# 555_A-stable.net
KiCad netlist of a schematic drawn in Altium Designer
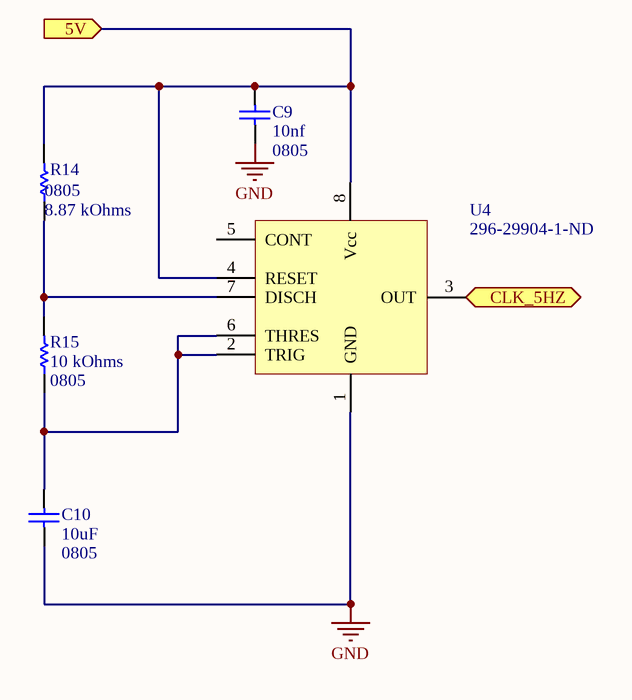
[diagram p0: 555_A-stable.SchDoc]

(export (version "E")
  (design (tool "Eeschema 10.0.6"))
  (components
    (comp (ref "C9")
      (value "CGA4C2C0G1H103J060AA")
      (footprint "CAP0805")
      (description "CAP CER 10000PF 50V C0G 0805")
      (fields
        (field (name "TOLERANCE") "±5%")
        (field (name "CAPACITANCE") "10nf")
        (field (name "PACKAGE / CASE") "0805")
      )
      (libsource (lib "Capacitors") (part "CGA4C2C0G1H103J060AA"))
    )
    (comp (ref "C10")
      (value "C2012JB1V106K125AC")
      (footprint "CAP0805")
      (description "CAP CER 10UF 35V JB 0805")
      (fields
        (field (name "TOLERANCE") "±20%")
        (field (name "CAPACITANCE") "10uF")
        (field (name "PACKAGE / CASE") "0805")
      )
      (libsource (lib "Capacitors") (part "C2012JB1V106K125AC"))
    )
    (comp (ref "R14")
      (value "ERJ-6ENF8871V")
      (footprint "RES0805")
      (description "RES SMD 8.87K OHM 1% 1/8W 0805")
      (fields
        (field (name "TOLERANCE") "±1%")
        (field (name "PACKAGE / CASE") "0805")
        (field (name "RESISTANCE") "8.87 kOhms")
      )
      (libsource (lib "Resistors") (part "ERJ-6ENF8871V"))
    )
    (comp (ref "R15")
      (value "RC0805FR-0710KL")
      (footprint "RES0805")
      (description "RES SMD 10K OHM 1% 1/8W 0805")
      (fields
        (field (name "MANUFACTURER") "Yageo")
        (field (name "TOLERANCE") "±1%")
        (field (name "RESISTANCE") "10 kOhms")
        (field (name "PACKAGE / CASE") "0805")
      )
      (libsource (lib "Resistors") (part "RC0805FR-0710KL"))
    )
    (comp (ref "U4")
      (value "NE555PWR")
      (footprint "TSOP65P650X120-8N")
      (description "IC OSC SGL TIMER 100KHZ 8TSSOP")
      (fields (field (name "SUPPLIER PART NUMBER 1") "296-29904-1-ND"))
      (libsource (lib "ICs") (part "NE555PWR"))
    )
  )
  (nets
    (net (code "1") (name "/5V") (class "Default")
      (node (ref "C9") (pin "2") (pinfunction "2_2") (pintype "passive"))
      (node (ref "R14") (pin "2") (pinfunction "2_2") (pintype "passive"))
      (node (ref "U4") (pin "4") (pinfunction "RESET_4") (pintype "passive"))
      (node (ref "U4") (pin "8") (pinfunction "Vcc_8") (pintype "passive"))
    )
    (net (code "2") (name "/CLK_5HZ") (class "Default")
      (node (ref "U4") (pin "3") (pinfunction "OUT_3") (pintype "passive"))
    )
    (net (code "3") (name "GND") (class "Default")
      (node (ref "C10") (pin "1") (pinfunction "1_1") (pintype "passive"))
      (node (ref "C9") (pin "1") (pinfunction "1_1") (pintype "passive"))
      (node (ref "U4") (pin "1") (pinfunction "GND_1") (pintype "passive"))
    )
    (net (code "4") (name "Net-(U4-DISCH)") (class "Default")
      (node (ref "R14") (pin "1") (pinfunction "1_1") (pintype "passive"))
      (node (ref "R15") (pin "2") (pinfunction "2_2") (pintype "passive"))
      (node (ref "U4") (pin "7") (pinfunction "DISCH_7") (pintype "passive"))
    )
    (net (code "5") (name "Net-(U4-THRES)") (class "Default")
      (node (ref "C10") (pin "2") (pinfunction "2_2") (pintype "passive"))
      (node (ref "R15") (pin "1") (pinfunction "1_1") (pintype "passive"))
      (node (ref "U4") (pin "2") (pinfunction "TRIG_2") (pintype "passive"))
      (node (ref "U4") (pin "6") (pinfunction "THRES_6") (pintype "passive"))
    )
    (net (code "6") (name "unconnected-(U4-CONT-Pad5)") (class "Default")
      (node (ref "U4") (pin "5") (pinfunction "CONT_5") (pintype "passive"))
    )
  )
)
